# atmega2560_sch.net
KiCad netlist of a schematic drawn in Altium Designer
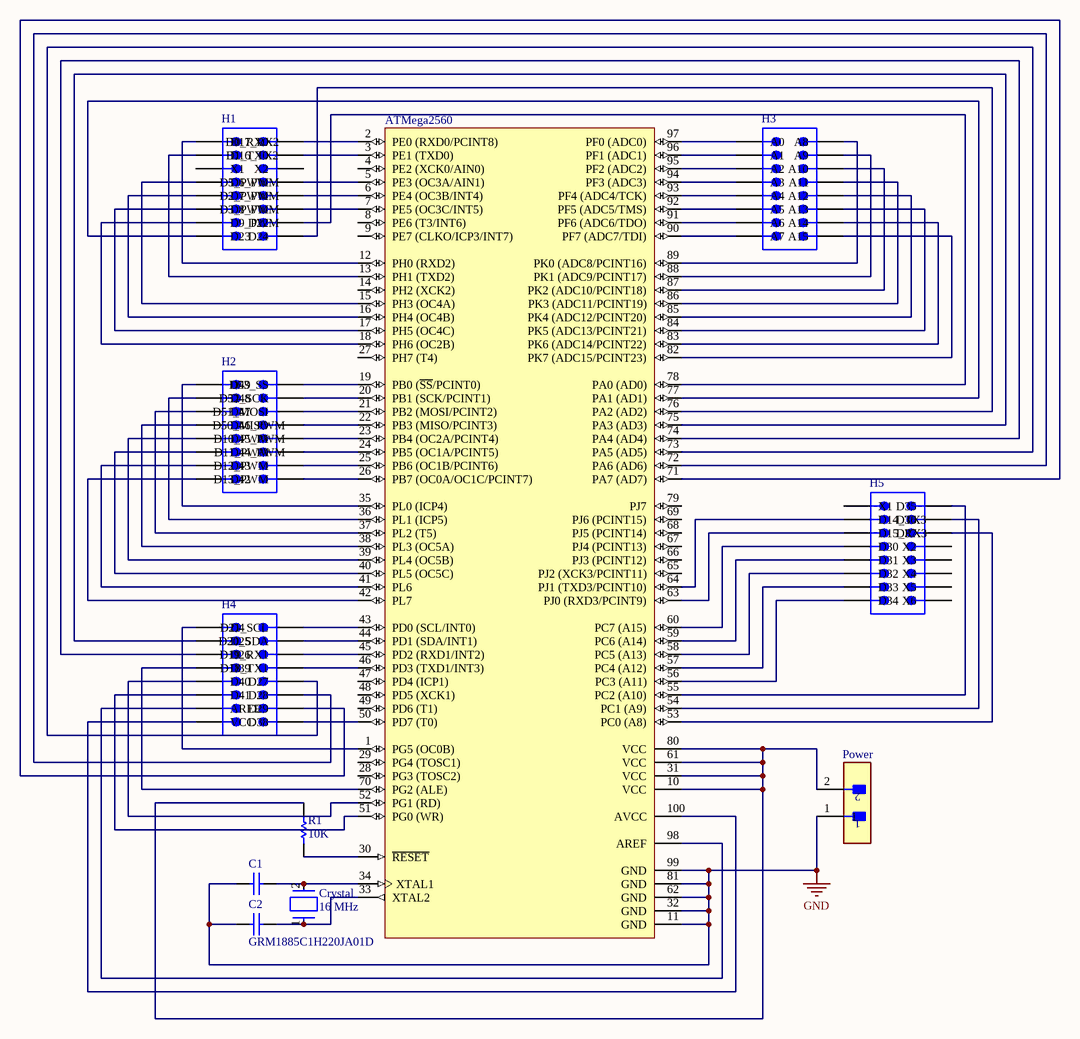
[diagram p0: atmega2560_sch.SchDoc]

(export (version "E")
  (design (tool "Eeschema 10.0.6"))
  (components
    (comp (ref "ATMega2560")
      (value "ATmega2560-16AU")
      (footprint "100A_M")
      (libsource (lib "Altium Content Vault") (part "MC-8B-ATM640-SQ100"))
    )
    (comp (ref "C1")
      (value "~")
      (footprint "CAPC1608X90X35ML10T15")
      (description "Chip Capacitor, 22 pF, +/- 5%, 50 V, -55 to 125 degC, 0603 (1608 Metric), RoHS, Tape and Reel")
      (fields (field (name "MANUFACTURER") "Murata"))
      (libsource (lib "Altium Content Vault") (part "CAP-NP-2"))
    )
    (comp (ref "C2")
      (value "GRM1885C1H220JA01D")
      (footprint "CAPC1608X90X35ML10T15")
      (description "Chip Capacitor, 22 pF, +/- 5%, 50 V, -55 to 125 degC, 0603 (1608 Metric), RoHS, Tape and Reel")
      (fields (field (name "MANUFACTURER") "Murata"))
      (libsource (lib "Altium Content Vault") (part "CAP-NP-2"))
    )
    (comp (ref "Crystal")
      (value "16 MHz")
      (footprint "FP-ABLS-MFG")
      (description "CRYSTAL 16.0000MHZ 18PF SMD")
      (fields
        (field (name "TOLERANCE") "30ppm")
        (field (name "MANUFACTURER PART NUMBER") "ABLS-16.000MHZ-K4T")
      )
      (libsource (lib "Altium Content Vault") (part "c23a69dc6c9e2f18f2079038eb95dd1"))
    )
    (comp (ref "H1")
      (value "61301621121")
      (footprint "61301621121")
      (libsource (lib "Altium Content Vault") (part "Header_Male_2R_16P"))
    )
    (comp (ref "H2")
      (value "61301621121")
      (footprint "61301621121")
      (libsource (lib "Altium Content Vault") (part "Header_Male_2R_16P"))
    )
    (comp (ref "H3")
      (value "61301621121")
      (footprint "61301621121")
      (libsource (lib "Altium Content Vault") (part "Header_Male_2R_16P"))
    )
    (comp (ref "H4")
      (value "61301621121")
      (footprint "61301621121")
      (libsource (lib "Altium Content Vault") (part "Header_Male_2R_16P"))
    )
    (comp (ref "H5")
      (value "61301621121")
      (footprint "61301621121")
      (libsource (lib "Altium Content Vault") (part "Header_Male_2R_16P"))
    )
    (comp (ref "Power")
      (value "TSW-102-07-G-S")
      (footprint "FP-TSW-102-07-G-S-MFG")
      (description "CONN HEADER VERT 2POS 2.54MM")
      (fields
        (field (name "MANUFACTURER") "Samtec")
        (field (name "OCTOPART") "https://octopart.com/tsw-102-07-g-s-samtec-272197")
      )
      (libsource (lib "Altium Content Vault") (part "3bc925449376181038e59eaffc5286c"))
    )
    (comp (ref "R1")
      (value "10K")
      (footprint "RESC1608X55X25ML10T15")
      (description "Resistor, 10 KOhm, +/- 5%, 100 mW, -55 to 155 degC, 0603 (1608 Metric), RoHS, Tape and Reel")
      (fields (field (name "MANUFACTURER") "Yageo") (field (name "TOLERANCE") "5%"))
      (libsource (lib "Altium Content Vault") (part "RES-2"))
    )
  )
  (nets
    (net (code "1") (name "GND") (class "Default")
      (node (ref "ATMega2560") (pin "11") (pinfunction "GND_11") (pintype "power_in"))
      (node (ref "ATMega2560") (pin "32") (pinfunction "GND_32") (pintype "power_in"))
      (node (ref "ATMega2560") (pin "62") (pinfunction "GND_62") (pintype "power_in"))
      (node (ref "ATMega2560") (pin "81") (pinfunction "GND_81") (pintype "power_in"))
      (node (ref "ATMega2560") (pin "99") (pinfunction "GND_99") (pintype "power_in"))
      (node (ref "C1") (pin "1") (pinfunction "1_1") (pintype "passive"))
      (node (ref "C2") (pin "1") (pinfunction "1_1") (pintype "passive"))
      (node (ref "Power") (pin "1") (pinfunction "1_1") (pintype "passive"))
    )
    (net (code "2") (name "Net-(ATMega2560-AREF)") (class "Default")
      (node (ref "ATMega2560") (pin "98") (pinfunction "AREF_98") (pintype "power_in"))
      (node (ref "H4") (pin "13") (pinfunction "D9_PWM_13") (pintype "passive"))
    )
    (net (code "3") (name "Net-(ATMega2560-AVCC)") (class "Default")
      (node (ref "ATMega2560") (pin "100") (pinfunction "AVCC_100") (pintype "power_in"))
      (node (ref "H4") (pin "15") (pinfunction "D23_15") (pintype "passive"))
    )
    (net (code "4") (name "Net-(ATMega2560-PA0_(AD0))") (class "Default")
      (node (ref "ATMega2560") (pin "78") (pinfunction "PA0_(AD0)_78") (pintype "bidirectional"))
      (node (ref "H1") (pin "14") (pinfunction "D22_14") (pintype "passive"))
    )
    (net (code "5") (name "Net-(ATMega2560-PA1_(AD1))") (class "Default")
      (node (ref "ATMega2560") (pin "77") (pinfunction "PA1_(AD1)_77") (pintype "bidirectional"))
      (node (ref "H1") (pin "15") (pinfunction "D23_15") (pintype "passive"))
    )
    (net (code "6") (name "Net-(ATMega2560-PA2_(AD2))") (class "Default")
      (node (ref "ATMega2560") (pin "76") (pinfunction "PA2_(AD2)_76") (pintype "bidirectional"))
      (node (ref "H1") (pin "16") (pinfunction "D24_16") (pintype "passive"))
    )
    (net (code "7") (name "Net-(ATMega2560-PA3_(AD3))") (class "Default")
      (node (ref "ATMega2560") (pin "75") (pinfunction "PA3_(AD3)_75") (pintype "bidirectional"))
      (node (ref "H4") (pin "3") (pinfunction "D16_TX2_3") (pintype "passive"))
    )
    (net (code "8") (name "Net-(ATMega2560-PA4_(AD4))") (class "Default")
      (node (ref "ATMega2560") (pin "74") (pinfunction "PA4_(AD4)_74") (pintype "bidirectional"))
      (node (ref "H4") (pin "5") (pinfunction "X1_5") (pintype "passive"))
    )
    (net (code "9") (name "Net-(ATMega2560-PA5_(AD5))") (class "Default")
      (node (ref "ATMega2560") (pin "73") (pinfunction "PA5_(AD5)_73") (pintype "bidirectional"))
      (node (ref "H4") (pin "10") (pinfunction "D2_PWM_10") (pintype "passive"))
    )
    (net (code "10") (name "Net-(ATMega2560-PA6_(AD6))") (class "Default")
      (node (ref "ATMega2560") (pin "72") (pinfunction "PA6_(AD6)_72") (pintype "bidirectional"))
      (node (ref "H4") (pin "12") (pinfunction "D3_PWM_12") (pintype "passive"))
    )
    (net (code "11") (name "Net-(ATMega2560-PA7_(AD7))") (class "Default")
      (node (ref "ATMega2560") (pin "71") (pinfunction "PA7_(AD7)_71") (pintype "bidirectional"))
      (node (ref "H4") (pin "14") (pinfunction "D22_14") (pintype "passive"))
    )
    (net (code "12") (name "Net-(ATMega2560-PB0_(~{SS}{slash}PCINT0))") (class "Default")
      (node (ref "ATMega2560") (pin "19") (pinfunction "PB0_(~{SS}/PCINT0)_19") (pintype "bidirectional"))
      (node (ref "H2") (pin "2") (pinfunction "D0_RX0_2") (pintype "passive"))
    )
    (net (code "13") (name "Net-(ATMega2560-PB1_(SCK{slash}PCINT1))") (class "Default")
      (node (ref "ATMega2560") (pin "20") (pinfunction "PB1_(SCK/PCINT1)_20") (pintype "bidirectional"))
      (node (ref "H2") (pin "4") (pinfunction "D1_TX0_4") (pintype "passive"))
    )
    (net (code "14") (name "Net-(ATMega2560-PB2_(MOSI{slash}PCINT2))") (class "Default")
      (node (ref "ATMega2560") (pin "21") (pinfunction "PB2_(MOSI/PCINT2)_21") (pintype "bidirectional"))
      (node (ref "H2") (pin "6") (pinfunction "X2_6") (pintype "passive"))
    )
    (net (code "15") (name "Net-(ATMega2560-PB3_(MISO{slash}PCINT3))") (class "Default")
      (node (ref "ATMega2560") (pin "22") (pinfunction "PB3_(MISO/PCINT3)_22") (pintype "bidirectional"))
      (node (ref "H2") (pin "8") (pinfunction "D5_PWM_8") (pintype "passive"))
    )
    (net (code "16") (name "Net-(ATMega2560-PB4_(OC2A{slash}PCINT4))") (class "Default")
      (node (ref "ATMega2560") (pin "23") (pinfunction "PB4_(OC2A/PCINT4)_23") (pintype "bidirectional"))
      (node (ref "H2") (pin "10") (pinfunction "D2_PWM_10") (pintype "passive"))
    )
    (net (code "17") (name "Net-(ATMega2560-PB5_(OC1A{slash}PCINT5))") (class "Default")
      (node (ref "ATMega2560") (pin "24") (pinfunction "PB5_(OC1A/PCINT5)_24") (pintype "bidirectional"))
      (node (ref "H2") (pin "12") (pinfunction "D3_PWM_12") (pintype "passive"))
    )
    (net (code "18") (name "Net-(ATMega2560-PB6_(OC1B{slash}PCINT6))") (class "Default")
      (node (ref "ATMega2560") (pin "25") (pinfunction "PB6_(OC1B/PCINT6)_25") (pintype "bidirectional"))
      (node (ref "H2") (pin "14") (pinfunction "D22_14") (pintype "passive"))
    )
    (net (code "19") (name "Net-(ATMega2560-PB7_(OC0A{slash}OC1C{slash}PCINT7))") (class "Default")
      (node (ref "ATMega2560") (pin "26") (pinfunction "PB7_(OC0A/OC1C/PCINT7)_26") (pintype "bidirectional"))
      (node (ref "H2") (pin "16") (pinfunction "D24_16") (pintype "passive"))
    )
    (net (code "20") (name "Net-(ATMega2560-PC0_(A8))") (class "Default")
      (node (ref "ATMega2560") (pin "53") (pinfunction "PC0_(A8)_53") (pintype "bidirectional"))
      (node (ref "H5") (pin "6") (pinfunction "X2_6") (pintype "passive"))
    )
    (net (code "21") (name "Net-(ATMega2560-PC1_(A9))") (class "Default")
      (node (ref "ATMega2560") (pin "54") (pinfunction "PC1_(A9)_54") (pintype "bidirectional"))
      (node (ref "H5") (pin "4") (pinfunction "D1_TX0_4") (pintype "passive"))
    )
    (net (code "22") (name "Net-(ATMega2560-PC2_(A10))") (class "Default")
      (node (ref "ATMega2560") (pin "55") (pinfunction "PC2_(A10)_55") (pintype "bidirectional"))
      (node (ref "H5") (pin "2") (pinfunction "D0_RX0_2") (pintype "passive"))
    )
    (net (code "23") (name "Net-(ATMega2560-PC3_(A11))") (class "Default")
      (node (ref "ATMega2560") (pin "56") (pinfunction "PC3_(A11)_56") (pintype "bidirectional"))
      (node (ref "H5") (pin "15") (pinfunction "D23_15") (pintype "passive"))
    )
    (net (code "24") (name "Net-(ATMega2560-PC4_(A12))") (class "Default")
      (node (ref "ATMega2560") (pin "57") (pinfunction "PC4_(A12)_57") (pintype "bidirectional"))
      (node (ref "H5") (pin "13") (pinfunction "D9_PWM_13") (pintype "passive"))
    )
    (net (code "25") (name "Net-(ATMega2560-PC5_(A13))") (class "Default")
      (node (ref "ATMega2560") (pin "58") (pinfunction "PC5_(A13)_58") (pintype "bidirectional"))
      (node (ref "H5") (pin "11") (pinfunction "D8_PWM_11") (pintype "passive"))
    )
    (net (code "26") (name "Net-(ATMega2560-PC6_(A14))") (class "Default")
      (node (ref "ATMega2560") (pin "59") (pinfunction "PC6_(A14)_59") (pintype "bidirectional"))
      (node (ref "H5") (pin "9") (pinfunction "D7_PWM_9") (pintype "passive"))
    )
    (net (code "27") (name "Net-(ATMega2560-PC7_(A15))") (class "Default")
      (node (ref "ATMega2560") (pin "60") (pinfunction "PC7_(A15)_60") (pintype "bidirectional"))
      (node (ref "H5") (pin "7") (pinfunction "D6_PWM_7") (pintype "passive"))
    )
    (net (code "28") (name "Net-(ATMega2560-PD0_(SCL{slash}INT0))") (class "Default")
      (node (ref "ATMega2560") (pin "43") (pinfunction "PD0_(SCL/INT0)_43") (pintype "bidirectional"))
      (node (ref "H4") (pin "2") (pinfunction "D0_RX0_2") (pintype "passive"))
    )
    (net (code "29") (name "Net-(ATMega2560-PD1_(SDA{slash}INT1))") (class "Default")
      (node (ref "ATMega2560") (pin "44") (pinfunction "PD1_(SDA/INT1)_44") (pintype "bidirectional"))
      (node (ref "H4") (pin "4") (pinfunction "D1_TX0_4") (pintype "passive"))
    )
    (net (code "30") (name "Net-(ATMega2560-PD2_(RXD1{slash}INT2))") (class "Default")
      (node (ref "ATMega2560") (pin "45") (pinfunction "PD2_(RXD1/INT2)_45") (pintype "bidirectional"))
      (node (ref "H4") (pin "6") (pinfunction "X2_6") (pintype "passive"))
    )
    (net (code "31") (name "Net-(ATMega2560-PD3_(TXD1{slash}INT3))") (class "Default")
      (node (ref "ATMega2560") (pin "46") (pinfunction "PD3_(TXD1/INT3)_46") (pintype "bidirectional"))
      (node (ref "H4") (pin "8") (pinfunction "D5_PWM_8") (pintype "passive"))
    )
    (net (code "32") (name "Net-(ATMega2560-PD7_(T0))") (class "Default")
      (node (ref "ATMega2560") (pin "50") (pinfunction "PD7_(T0)_50") (pintype "bidirectional"))
      (node (ref "H4") (pin "16") (pinfunction "D24_16") (pintype "passive"))
    )
    (net (code "33") (name "Net-(ATMega2560-PE0_(RXD0{slash}PCINT8))") (class "Default")
      (node (ref "ATMega2560") (pin "2") (pinfunction "PE0_(RXD0/PCINT8)_2") (pintype "bidirectional"))
      (node (ref "H1") (pin "2") (pinfunction "D0_RX0_2") (pintype "passive"))
    )
    (net (code "34") (name "Net-(ATMega2560-PE1_(TXD0))") (class "Default")
      (node (ref "ATMega2560") (pin "3") (pinfunction "PE1_(TXD0)_3") (pintype "bidirectional"))
      (node (ref "H1") (pin "4") (pinfunction "D1_TX0_4") (pintype "passive"))
    )
    (net (code "35") (name "Net-(ATMega2560-PE3_(OC3A{slash}AIN1))") (class "Default")
      (node (ref "ATMega2560") (pin "5") (pinfunction "PE3_(OC3A/AIN1)_5") (pintype "bidirectional"))
      (node (ref "H1") (pin "8") (pinfunction "D5_PWM_8") (pintype "passive"))
    )
    (net (code "36") (name "Net-(ATMega2560-PE4_(OC3B{slash}INT4))") (class "Default")
      (node (ref "ATMega2560") (pin "6") (pinfunction "PE4_(OC3B/INT4)_6") (pintype "bidirectional"))
      (node (ref "H1") (pin "10") (pinfunction "D2_PWM_10") (pintype "passive"))
    )
    (net (code "37") (name "Net-(ATMega2560-PE5_(OC3C{slash}INT5))") (class "Default")
      (node (ref "ATMega2560") (pin "7") (pinfunction "PE5_(OC3C/INT5)_7") (pintype "bidirectional"))
      (node (ref "H1") (pin "12") (pinfunction "D3_PWM_12") (pintype "passive"))
    )
    (net (code "38") (name "Net-(ATMega2560-PF0_(ADC0))") (class "Default")
      (node (ref "ATMega2560") (pin "97") (pinfunction "PF0_(ADC0)_97") (pintype "bidirectional"))
      (node (ref "H3") (pin "1") (pinfunction "D17_RX2_1") (pintype "passive"))
    )
    (net (code "39") (name "Net-(ATMega2560-PF1_(ADC1))") (class "Default")
      (node (ref "ATMega2560") (pin "96") (pinfunction "PF1_(ADC1)_96") (pintype "bidirectional"))
      (node (ref "H3") (pin "3") (pinfunction "D16_TX2_3") (pintype "passive"))
    )
    (net (code "40") (name "Net-(ATMega2560-PF2_(ADC2))") (class "Default")
      (node (ref "ATMega2560") (pin "95") (pinfunction "PF2_(ADC2)_95") (pintype "bidirectional"))
      (node (ref "H3") (pin "5") (pinfunction "X1_5") (pintype "passive"))
    )
    (net (code "41") (name "Net-(ATMega2560-PF3_(ADC3))") (class "Default")
      (node (ref "ATMega2560") (pin "94") (pinfunction "PF3_(ADC3)_94") (pintype "bidirectional"))
      (node (ref "H3") (pin "7") (pinfunction "D6_PWM_7") (pintype "passive"))
    )
    (net (code "42") (name "Net-(ATMega2560-PF4_(ADC4{slash}TCK))") (class "Default")
      (node (ref "ATMega2560") (pin "93") (pinfunction "PF4_(ADC4/TCK)_93") (pintype "bidirectional"))
      (node (ref "H3") (pin "9") (pinfunction "D7_PWM_9") (pintype "passive"))
    )
    (net (code "43") (name "Net-(ATMega2560-PF5_(ADC5{slash}TMS))") (class "Default")
      (node (ref "ATMega2560") (pin "92") (pinfunction "PF5_(ADC5/TMS)_92") (pintype "bidirectional"))
      (node (ref "H3") (pin "11") (pinfunction "D8_PWM_11") (pintype "passive"))
    )
    (net (code "44") (name "Net-(ATMega2560-PF6_(ADC6{slash}TDO))") (class "Default")
      (node (ref "ATMega2560") (pin "91") (pinfunction "PF6_(ADC6/TDO)_91") (pintype "bidirectional"))
      (node (ref "H3") (pin "13") (pinfunction "D9_PWM_13") (pintype "passive"))
    )
    (net (code "45") (name "Net-(ATMega2560-PF7_(ADC7{slash}TDI))") (class "Default")
      (node (ref "ATMega2560") (pin "90") (pinfunction "PF7_(ADC7/TDI)_90") (pintype "bidirectional"))
      (node (ref "H3") (pin "15") (pinfunction "D23_15") (pintype "passive"))
    )
    (net (code "46") (name "Net-(ATMega2560-PG0_(WR))") (class "Default")
      (node (ref "ATMega2560") (pin "51") (pinfunction "PG0_(WR)_51") (pintype "bidirectional"))
      (node (ref "H4") (pin "11") (pinfunction "D8_PWM_11") (pintype "passive"))
    )
    (net (code "47") (name "Net-(ATMega2560-PG1_(RD))") (class "Default")
      (node (ref "ATMega2560") (pin "52") (pinfunction "PG1_(RD)_52") (pintype "bidirectional"))
      (node (ref "H4") (pin "9") (pinfunction "D7_PWM_9") (pintype "passive"))
    )
    (net (code "48") (name "Net-(ATMega2560-PG2_(ALE))") (class "Default")
      (node (ref "ATMega2560") (pin "70") (pinfunction "PG2_(ALE)_70") (pintype "bidirectional"))
      (node (ref "H4") (pin "7") (pinfunction "D6_PWM_7") (pintype "passive"))
    )
    (net (code "49") (name "Net-(ATMega2560-PG5_(OC0B))") (class "Default")
      (node (ref "ATMega2560") (pin "1") (pinfunction "PG5_(OC0B)_1") (pintype "bidirectional"))
      (node (ref "H4") (pin "1") (pinfunction "D17_RX2_1") (pintype "passive"))
    )
    (net (code "50") (name "Net-(ATMega2560-PH0_(RXD2))") (class "Default")
      (node (ref "ATMega2560") (pin "12") (pinfunction "PH0_(RXD2)_12") (pintype "bidirectional"))
      (node (ref "H1") (pin "1") (pinfunction "D17_RX2_1") (pintype "passive"))
    )
    (net (code "51") (name "Net-(ATMega2560-PH1_(TXD2))") (class "Default")
      (node (ref "ATMega2560") (pin "13") (pinfunction "PH1_(TXD2)_13") (pintype "bidirectional"))
      (node (ref "H1") (pin "3") (pinfunction "D16_TX2_3") (pintype "passive"))
    )
    (net (code "52") (name "Net-(ATMega2560-PH3_(OC4A))") (class "Default")
      (node (ref "ATMega2560") (pin "15") (pinfunction "PH3_(OC4A)_15") (pintype "bidirectional"))
      (node (ref "H1") (pin "7") (pinfunction "D6_PWM_7") (pintype "passive"))
    )
    (net (code "53") (name "Net-(ATMega2560-PH4_(OC4B))") (class "Default")
      (node (ref "ATMega2560") (pin "16") (pinfunction "PH4_(OC4B)_16") (pintype "bidirectional"))
      (node (ref "H1") (pin "9") (pinfunction "D7_PWM_9") (pintype "passive"))
    )
    (net (code "54") (name "Net-(ATMega2560-PH5_(OC4C))") (class "Default")
      (node (ref "ATMega2560") (pin "17") (pinfunction "PH5_(OC4C)_17") (pintype "bidirectional"))
      (node (ref "H1") (pin "11") (pinfunction "D8_PWM_11") (pintype "passive"))
    )
    (net (code "55") (name "Net-(ATMega2560-PH6_(OC2B))") (class "Default")
      (node (ref "ATMega2560") (pin "18") (pinfunction "PH6_(OC2B)_18") (pintype "bidirectional"))
      (node (ref "H1") (pin "13") (pinfunction "D9_PWM_13") (pintype "passive"))
    )
    (net (code "56") (name "Net-(ATMega2560-PJ0_(RXD3{slash}PCINT9))") (class "Default")
      (node (ref "ATMega2560") (pin "63") (pinfunction "PJ0_(RXD3/PCINT9)_63") (pintype "bidirectional"))
      (node (ref "H5") (pin "5") (pinfunction "X1_5") (pintype "passive"))
    )
    (net (code "57") (name "Net-(ATMega2560-PJ1_(TXD3{slash}PCINT10))") (class "Default")
      (node (ref "ATMega2560") (pin "64") (pinfunction "PJ1_(TXD3/PCINT10)_64") (pintype "bidirectional"))
      (node (ref "H5") (pin "3") (pinfunction "D16_TX2_3") (pintype "passive"))
    )
    (net (code "58") (name "Net-(ATMega2560-PK0_(ADC8{slash}PCINT16))") (class "Default")
      (node (ref "ATMega2560") (pin "89") (pinfunction "PK0_(ADC8/PCINT16)_89") (pintype "bidirectional"))
      (node (ref "H3") (pin "2") (pinfunction "D0_RX0_2") (pintype "passive"))
    )
    (net (code "59") (name "Net-(ATMega2560-PK1_(ADC9{slash}PCINT17))") (class "Default")
      (node (ref "ATMega2560") (pin "88") (pinfunction "PK1_(ADC9/PCINT17)_88") (pintype "bidirectional"))
      (node (ref "H3") (pin "4") (pinfunction "D1_TX0_4") (pintype "passive"))
    )
    (net (code "60") (name "Net-(ATMega2560-PK2_(ADC10{slash}PCINT18))") (class "Default")
      (node (ref "ATMega2560") (pin "87") (pinfunction "PK2_(ADC10/PCINT18)_87") (pintype "bidirectional"))
      (node (ref "H3") (pin "6") (pinfunction "X2_6") (pintype "passive"))
    )
    (net (code "61") (name "Net-(ATMega2560-PK3_(ADC11{slash}PCINT19))") (class "Default")
      (node (ref "ATMega2560") (pin "86") (pinfunction "PK3_(ADC11/PCINT19)_86") (pintype "bidirectional"))
      (node (ref "H3") (pin "8") (pinfunction "D5_PWM_8") (pintype "passive"))
    )
    (net (code "62") (name "Net-(ATMega2560-PK4_(ADC12{slash}PCINT20))") (class "Default")
      (node (ref "ATMega2560") (pin "85") (pinfunction "PK4_(ADC12/PCINT20)_85") (pintype "bidirectional"))
      (node (ref "H3") (pin "10") (pinfunction "D2_PWM_10") (pintype "passive"))
    )
    (net (code "63") (name "Net-(ATMega2560-PK5_(ADC13{slash}PCINT21))") (class "Default")
      (node (ref "ATMega2560") (pin "84") (pinfunction "PK5_(ADC13/PCINT21)_84") (pintype "bidirectional"))
      (node (ref "H3") (pin "12") (pinfunction "D3_PWM_12") (pintype "passive"))
    )
    (net (code "64") (name "Net-(ATMega2560-PK6_(ADC14{slash}PCINT22))") (class "Default")
      (node (ref "ATMega2560") (pin "83") (pinfunction "PK6_(ADC14/PCINT22)_83") (pintype "bidirectional"))
      (node (ref "H3") (pin "14") (pinfunction "D22_14") (pintype "passive"))
    )
    (net (code "65") (name "Net-(ATMega2560-PK7_(ADC15{slash}PCINT23))") (class "Default")
      (node (ref "ATMega2560") (pin "82") (pinfunction "PK7_(ADC15/PCINT23)_82") (pintype "bidirectional"))
      (node (ref "H3") (pin "16") (pinfunction "D24_16") (pintype "passive"))
    )
    (net (code "66") (name "Net-(ATMega2560-PL0_(ICP4))") (class "Default")
      (node (ref "ATMega2560") (pin "35") (pinfunction "PL0_(ICP4)_35") (pintype "bidirectional"))
      (node (ref "H2") (pin "1") (pinfunction "D17_RX2_1") (pintype "passive"))
    )
    (net (code "67") (name "Net-(ATMega2560-PL1_(ICP5))") (class "Default")
      (node (ref "ATMega2560") (pin "36") (pinfunction "PL1_(ICP5)_36") (pintype "bidirectional"))
      (node (ref "H2") (pin "3") (pinfunction "D16_TX2_3") (pintype "passive"))
    )
    (net (code "68") (name "Net-(ATMega2560-PL2_(T5))") (class "Default")
      (node (ref "ATMega2560") (pin "37") (pinfunction "PL2_(T5)_37") (pintype "bidirectional"))
      (node (ref "H2") (pin "5") (pinfunction "X1_5") (pintype "passive"))
    )
    (net (code "69") (name "Net-(ATMega2560-PL3_(OC5A))") (class "Default")
      (node (ref "ATMega2560") (pin "38") (pinfunction "PL3_(OC5A)_38") (pintype "bidirectional"))
      (node (ref "H2") (pin "7") (pinfunction "D6_PWM_7") (pintype "passive"))
    )
    (net (code "70") (name "Net-(ATMega2560-PL4_(OC5B))") (class "Default")
      (node (ref "ATMega2560") (pin "39") (pinfunction "PL4_(OC5B)_39") (pintype "bidirectional"))
      (node (ref "H2") (pin "9") (pinfunction "D7_PWM_9") (pintype "passive"))
    )
    (net (code "71") (name "Net-(ATMega2560-PL5_(OC5C))") (class "Default")
      (node (ref "ATMega2560") (pin "40") (pinfunction "PL5_(OC5C)_40") (pintype "bidirectional"))
      (node (ref "H2") (pin "11") (pinfunction "D8_PWM_11") (pintype "passive"))
    )
    (net (code "72") (name "Net-(ATMega2560-PL6)") (class "Default")
      (node (ref "ATMega2560") (pin "41") (pinfunction "PL6_41") (pintype "bidirectional"))
      (node (ref "H2") (pin "13") (pinfunction "D9_PWM_13") (pintype "passive"))
    )
    (net (code "73") (name "Net-(ATMega2560-PL7)") (class "Default")
      (node (ref "ATMega2560") (pin "42") (pinfunction "PL7_42") (pintype "bidirectional"))
      (node (ref "H2") (pin "15") (pinfunction "D23_15") (pintype "passive"))
    )
    (net (code "74") (name "Net-(ATMega2560-VCC-Pad10)") (class "Default")
      (node (ref "ATMega2560") (pin "10") (pinfunction "VCC_10") (pintype "power_in"))
      (node (ref "ATMega2560") (pin "31") (pinfunction "VCC_31") (pintype "power_in"))
      (node (ref "ATMega2560") (pin "61") (pinfunction "VCC_61") (pintype "power_in"))
      (node (ref "ATMega2560") (pin "80") (pinfunction "VCC_80") (pintype "power_in"))
      (node (ref "Power") (pin "2") (pinfunction "2_2") (pintype "passive"))
      (node (ref "R1") (pin "2") (pinfunction "2_2") (pintype "passive"))
    )
    (net (code "75") (name "Net-(ATMega2560-XTAL1)") (class "Default")
      (node (ref "ATMega2560") (pin "34") (pinfunction "XTAL1_34") (pintype "input"))
      (node (ref "C1") (pin "2") (pinfunction "2_2") (pintype "passive"))
      (node (ref "Crystal") (pin "2") (pinfunction "2_2") (pintype "passive"))
    )
    (net (code "76") (name "Net-(ATMega2560-XTAL2)") (class "Default")
      (node (ref "ATMega2560") (pin "33") (pinfunction "XTAL2_33") (pintype "output"))
      (node (ref "C2") (pin "2") (pinfunction "2_2") (pintype "passive"))
      (node (ref "Crystal") (pin "1") (pinfunction "1_1") (pintype "passive"))
    )
    (net (code "77") (name "Net-(ATMega2560-~{RESET})") (class "Default")
      (node (ref "ATMega2560") (pin "30") (pinfunction "~{RESET}_30") (pintype "input"))
      (node (ref "R1") (pin "1") (pinfunction "1_1") (pintype "passive"))
    )
    (net (code "78") (name "unconnected-(ATMega2560-PD4_(ICP1)-Pad47)") (class "Default")
      (node (ref "ATMega2560") (pin "47") (pinfunction "PD4_(ICP1)_47") (pintype "bidirectional"))
    )
    (net (code "79") (name "unconnected-(ATMega2560-PD5_(XCK1)-Pad48)") (class "Default")
      (node (ref "ATMega2560") (pin "48") (pinfunction "PD5_(XCK1)_48") (pintype "bidirectional"))
    )
    (net (code "80") (name "unconnected-(ATMega2560-PD6_(T1)-Pad49)") (class "Default")
      (node (ref "ATMega2560") (pin "49") (pinfunction "PD6_(T1)_49") (pintype "bidirectional"))
    )
    (net (code "81") (name "unconnected-(ATMega2560-PE2_(XCK0{slash}AIN0)-Pad4)") (class "Default")
      (node (ref "ATMega2560") (pin "4") (pinfunction "PE2_(XCK0/AIN0)_4") (pintype "bidirectional"))
    )
    (net (code "82") (name "unconnected-(ATMega2560-PE6_(T3{slash}INT6)-Pad8)") (class "Default")
      (node (ref "ATMega2560") (pin "8") (pinfunction "PE6_(T3/INT6)_8") (pintype "bidirectional"))
    )
    (net (code "83") (name "unconnected-(ATMega2560-PE7_(CLKO{slash}ICP3{slash}INT7)-Pad9)") (class "Default")
      (node (ref "ATMega2560") (pin "9") (pinfunction "PE7_(CLKO/ICP3/INT7)_9") (pintype "bidirectional"))
    )
    (net (code "84") (name "unconnected-(ATMega2560-PG3_(TOSC2)-Pad28)") (class "Default")
      (node (ref "ATMega2560") (pin "28") (pinfunction "PG3_(TOSC2)_28") (pintype "bidirectional"))
    )
    (net (code "85") (name "unconnected-(ATMega2560-PG4_(TOSC1)-Pad29)") (class "Default")
      (node (ref "ATMega2560") (pin "29") (pinfunction "PG4_(TOSC1)_29") (pintype "bidirectional"))
    )
    (net (code "86") (name "unconnected-(ATMega2560-PH2_(XCK2)-Pad14)") (class "Default")
      (node (ref "ATMega2560") (pin "14") (pinfunction "PH2_(XCK2)_14") (pintype "bidirectional"))
    )
    (net (code "87") (name "unconnected-(ATMega2560-PH7_(T4)-Pad27)") (class "Default")
      (node (ref "ATMega2560") (pin "27") (pinfunction "PH7_(T4)_27") (pintype "bidirectional"))
    )
    (net (code "88") (name "unconnected-(ATMega2560-PJ2_(XCK3{slash}PCINT11)-Pad65)") (class "Default")
      (node (ref "ATMega2560") (pin "65") (pinfunction "PJ2_(XCK3/PCINT11)_65") (pintype "bidirectional"))
    )
    (net (code "89") (name "unconnected-(ATMega2560-PJ3_(PCINT12)-Pad66)") (class "Default")
      (node (ref "ATMega2560") (pin "66") (pinfunction "PJ3_(PCINT12)_66") (pintype "bidirectional"))
    )
    (net (code "90") (name "unconnected-(ATMega2560-PJ4_(PCINT13)-Pad67)") (class "Default")
      (node (ref "ATMega2560") (pin "67") (pinfunction "PJ4_(PCINT13)_67") (pintype "bidirectional"))
    )
    (net (code "91") (name "unconnected-(ATMega2560-PJ5_(PCINT14)-Pad68)") (class "Default")
      (node (ref "ATMega2560") (pin "68") (pinfunction "PJ5_(PCINT14)_68") (pintype "bidirectional"))
    )
    (net (code "92") (name "unconnected-(ATMega2560-PJ6_(PCINT15)-Pad69)") (class "Default")
      (node (ref "ATMega2560") (pin "69") (pinfunction "PJ6_(PCINT15)_69") (pintype "bidirectional"))
    )
    (net (code "93") (name "unconnected-(ATMega2560-PJ7-Pad79)") (class "Default")
      (node (ref "ATMega2560") (pin "79") (pinfunction "PJ7_79") (pintype "bidirectional"))
    )
    (net (code "94") (name "unconnected-(H1-X1-Pad5)") (class "Default")
      (node (ref "H1") (pin "5") (pinfunction "X1_5") (pintype "passive"))
    )
    (net (code "95") (name "unconnected-(H1-X2-Pad6)") (class "Default")
      (node (ref "H1") (pin "6") (pinfunction "X2_6") (pintype "passive"))
    )
    (net (code "96") (name "unconnected-(H5-D2_PWM-Pad10)") (class "Default")
      (node (ref "H5") (pin "10") (pinfunction "D2_PWM_10") (pintype "passive"))
    )
    (net (code "97") (name "unconnected-(H5-D3_PWM-Pad12)") (class "Default")
      (node (ref "H5") (pin "12") (pinfunction "D3_PWM_12") (pintype "passive"))
    )
    (net (code "98") (name "unconnected-(H5-D5_PWM-Pad8)") (class "Default")
      (node (ref "H5") (pin "8") (pinfunction "D5_PWM_8") (pintype "passive"))
    )
    (net (code "99") (name "unconnected-(H5-D17_RX2-Pad1)") (class "Default")
      (node (ref "H5") (pin "1") (pinfunction "D17_RX2_1") (pintype "passive"))
    )
    (net (code "100") (name "unconnected-(H5-D22-Pad14)") (class "Default")
      (node (ref "H5") (pin "14") (pinfunction "D22_14") (pintype "passive"))
    )
    (net (code "101") (name "unconnected-(H5-D24-Pad16)") (class "Default")
      (node (ref "H5") (pin "16") (pinfunction "D24_16") (pintype "passive"))
    )
  )
)
